# Projeto_Fonte.net
KiCad netlist of a schematic drawn in EAGLE
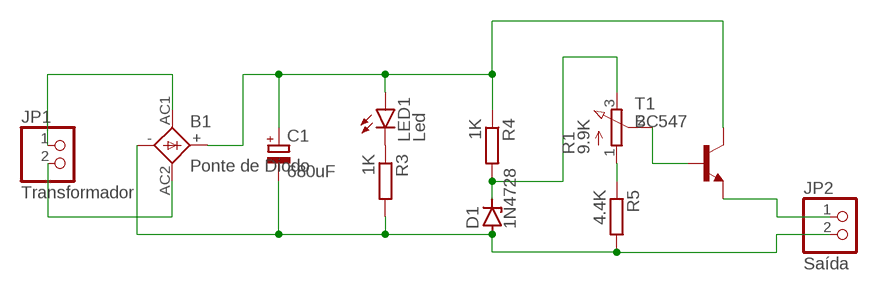
[diagram p0: schematic, sheet 1]

(export (version "E")
  (design (tool "Eeschema 10.0.6"))
  (components
    (comp (ref "B1")
      (value "Ponte de Diodo")
      (footprint "eagle-import:1KAB")
      (libsource (lib "eagle-import") (part "1KAB"))
    )
    (comp (ref "C1")
      (value "680uF")
      (footprint "eagle-import:E5-10,5")
      (libsource (lib "eagle-import") (part "CPOL-EUE5-10.5"))
    )
    (comp (ref "D1")
      (value "1N4728")
      (footprint "eagle-import:DO41Z10")
      (libsource (lib "eagle-import") (part "1N4728"))
    )
    (comp (ref "JP1")
      (value "Transformador")
      (footprint "eagle-import:1X02")
      (libsource (lib "eagle-import") (part "PINHD-1X2"))
    )
    (comp (ref "JP2")
      (value "Saída")
      (footprint "eagle-import:1X02")
      (libsource (lib "eagle-import") (part "PINHD-1X2"))
    )
    (comp (ref "LED1")
      (value "Led")
      (footprint "eagle-import:LED5MM")
      (libsource (lib "eagle-import") (part "LED5MM"))
    )
    (comp (ref "R1")
      (value "9.9K")
      (footprint "eagle-import:3RP_1610N")
      (libsource (lib "eagle-import") (part "3RP/1610N"))
    )
    (comp (ref "R3")
      (value "1K")
      (footprint "eagle-import:0204_7")
      (libsource (lib "eagle-import") (part "R-EU_0204/7"))
    )
    (comp (ref "R4")
      (value "1K")
      (footprint "eagle-import:0204_7")
      (libsource (lib "eagle-import") (part "R-EU_0204/7"))
    )
    (comp (ref "R5")
      (value "4.4K")
      (footprint "eagle-import:0204_7")
      (libsource (lib "eagle-import") (part "R-EU_0204/7"))
    )
    (comp (ref "T1")
      (value "BC547")
      (footprint "eagle-import:TO92")
      (libsource (lib "eagle-import") (part "BC547"))
    )
  )
  (nets
    (net (code "1") (name "Net-(B1-Pad-)") (class "Default")
      (node (ref "B1") (pin "-") (pinfunction "-_-") (pintype "passive"))
      (node (ref "C1") (pin "-") (pinfunction "-_-") (pintype "passive"))
      (node (ref "D1") (pin "A") (pinfunction "A_A") (pintype "passive"))
      (node (ref "JP2") (pin "2") (pinfunction "2_2") (pintype "passive"))
      (node (ref "R3") (pin "2") (pinfunction "2_2") (pintype "passive"))
      (node (ref "R5") (pin "2") (pinfunction "2_2") (pintype "passive"))
    )
    (net (code "2") (name "Net-(B1-PadAC1)") (class "Default")
      (node (ref "B1") (pin "AC1") (pinfunction "AC1_AC1") (pintype "passive"))
      (node (ref "JP1") (pin "1") (pinfunction "1_1") (pintype "passive"))
    )
    (net (code "3") (name "Net-(B1-PadAC2)") (class "Default")
      (node (ref "B1") (pin "AC2") (pinfunction "AC2_AC2") (pintype "passive"))
      (node (ref "JP1") (pin "2") (pinfunction "2_2") (pintype "passive"))
    )
    (net (code "4") (name "Net-(LED1-C)") (class "Default")
      (node (ref "LED1") (pin "K") (pinfunction "C_K") (pintype "passive"))
      (node (ref "R3") (pin "1") (pinfunction "1_1") (pintype "passive"))
    )
    (net (code "5") (name "Net-(R1-A)") (class "Default")
      (node (ref "R1") (pin "1") (pinfunction "A_1") (pintype "passive"))
      (node (ref "R5") (pin "1") (pinfunction "1_1") (pintype "passive"))
    )
    (net (code "6") (name "Net-(R1-E)") (class "Default")
      (node (ref "D1") (pin "C") (pinfunction "C_C") (pintype "passive"))
      (node (ref "R1") (pin "3") (pinfunction "E_3") (pintype "passive"))
      (node (ref "R4") (pin "2") (pinfunction "2_2") (pintype "passive"))
    )
    (net (code "7") (name "Net-(R1-S)") (class "Default")
      (node (ref "R1") (pin "2") (pinfunction "S_2") (pintype "passive"))
      (node (ref "T1") (pin "2") (pinfunction "B_2") (pintype "passive"))
    )
    (net (code "8") (name "Net-(T1-C)") (class "Default")
      (node (ref "B1") (pin "+") (pinfunction "+_+") (pintype "passive"))
      (node (ref "C1") (pin "+") (pinfunction "+_+") (pintype "passive"))
      (node (ref "LED1") (pin "A") (pinfunction "A_A") (pintype "passive"))
      (node (ref "R4") (pin "1") (pinfunction "1_1") (pintype "passive"))
      (node (ref "T1") (pin "3") (pinfunction "C_3") (pintype "passive"))
    )
    (net (code "9") (name "Net-(T1-E)") (class "Default")
      (node (ref "JP2") (pin "1") (pinfunction "1_1") (pintype "passive"))
      (node (ref "T1") (pin "1") (pinfunction "E_1") (pintype "passive"))
    )
  )
)
